# Smart_Project_Eagle.net
KiCad netlist of a schematic drawn in EasyEDA
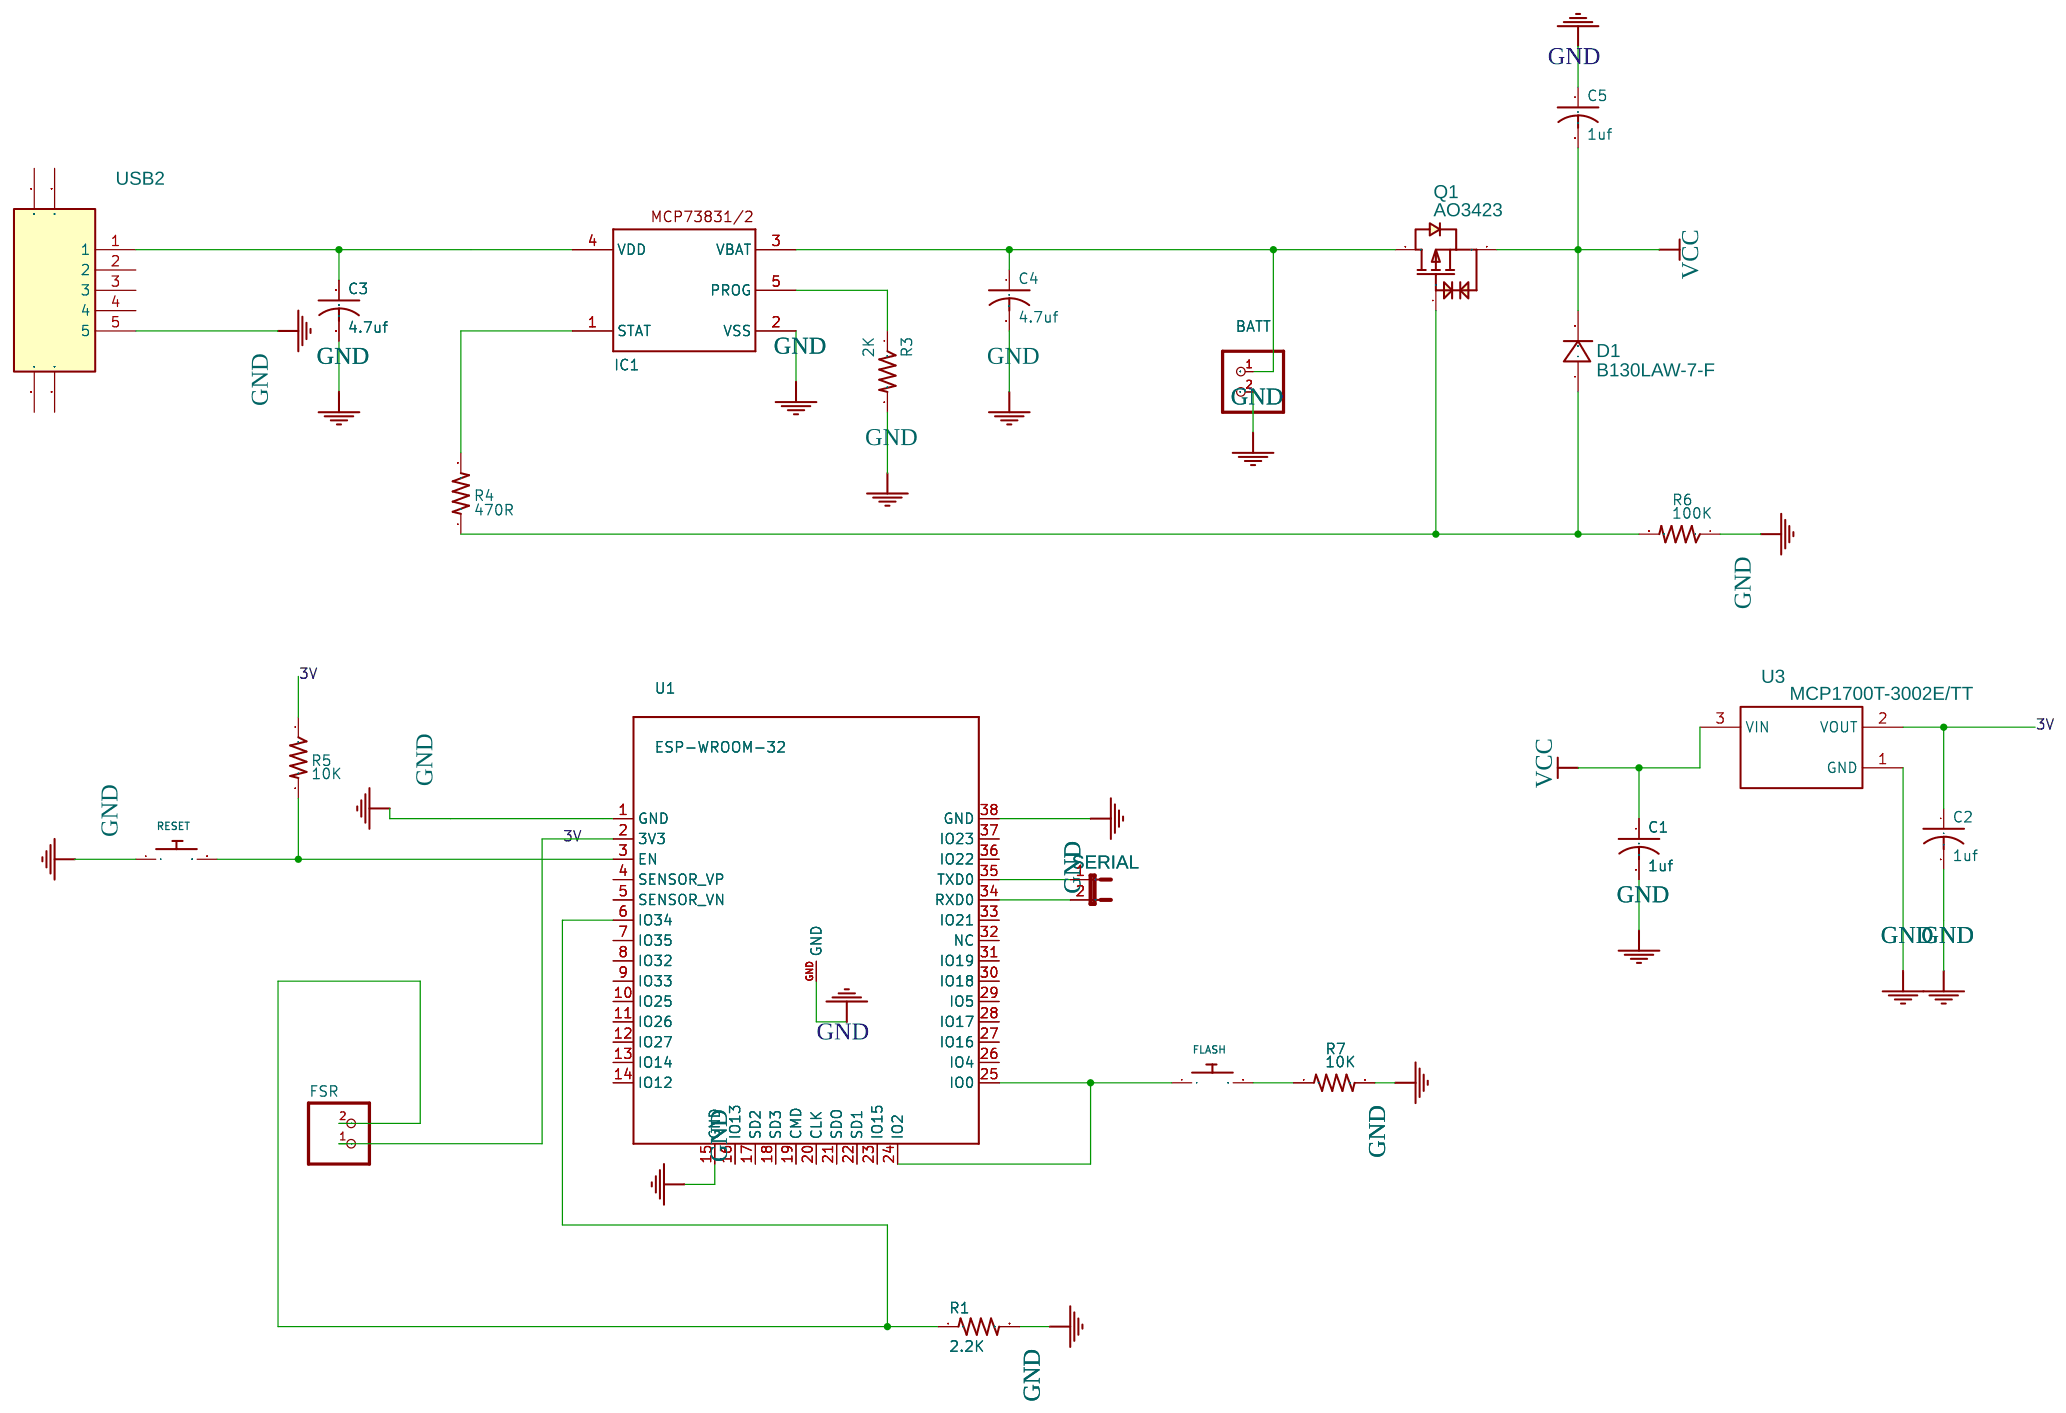
[diagram p0: schematic sheet]

(export (version "E")
  (design (tool "Eeschema 10.0.6"))
  (components
    (comp (ref "BATT") (value "JST_2PIN-SMT") (libsource (lib "") (part "Unknown_420_-470")))
    (comp (ref "C1") (value "1uf") (libsource (lib "") (part "Unknown_620_-240")))
    (comp (ref "C2") (value "1uf") (libsource (lib "") (part "Unknown_770_-245")))
    (comp (ref "C3") (value "4.7uf") (libsource (lib "") (part "Unknown_-20_-505")))
    (comp (ref "C4") (value "4.7uf") (libsource (lib "") (part "Unknown_310_-510")))
    (comp (ref "C5") (value "1uf") (libsource (lib "") (part "Unknown_590_-600")))
    (comp (ref "D1") (value "B130LAW-7-F") (libsource (lib "") (part "Unknown_590_-480")))
    (comp (ref "FLASH") (value "SWITCH_PUSHBUTTONC&K_KSS") (libsource (lib "") (part "Unknown_410_-120")))
    (comp (ref "FSR") (value "JST_2PIN-SMT") (libsource (lib "") (part "Unknown_-10_-90")))
    (comp (ref "IC1") (value "MCP73831/OT") (libsource (lib "") (part "Unknown_145_-510")))
    (comp (ref "JP1")
      (value "SERIAL")
      (fields (field (name "BOM_Manufacturer Part") "?"))
      (libsource (lib "") (part "Unknown_350_-220"))
    )
    (comp (ref "Q1") (value "AO3423") (libsource (lib "") (part "Unknown_520_-530")))
    (comp (ref "R1") (value "2.2K") (libsource (lib "") (part "Unknown_295_0")))
    (comp (ref "R3") (value "2K") (libsource (lib "") (part "Unknown_250_-470")))
    (comp (ref "R4") (value "470R") (libsource (lib "") (part "Unknown_40_-410")))
    (comp (ref "R5") (value "10K") (libsource (lib "") (part "Unknown_-40_-280")))
    (comp (ref "R6") (value "100K") (libsource (lib "") (part "Unknown_640_-390")))
    (comp (ref "R7") (value "10K") (libsource (lib "") (part "Unknown_470_-120")))
    (comp (ref "RESET") (value "SWITCH_PUSHBUTTONC&K_KSS") (libsource (lib "") (part "Unknown_-100_-230")))
    (comp (ref "U1") (value "ESP-WROOM-32") (libsource (lib "") (part "Unknown_185_-240")))
    (comp (ref "U3") (value "MCP1700T-3002E/TT") (libsource (lib "") (part "Unknown_700_-305")))
    (comp (ref "USB2")
      (value "micro 5PAll posts are not guided Flat welding_C40942")
      (fields (field (name "BOM_Manufacturer Part") "micro 5PAll posts are not guided Flat welding"))
      (libsource (lib "") (part "Unknown_-160_-510"))
    )
  )
  (nets
    (net (code "1") (name "/3V") (class "Default")
      (node (ref "C2") (pin "1") (pinfunction "1_1") (pintype "bidirectional"))
      (node (ref "FSR") (pin "1") (pinfunction "2_1") (pintype "bidirectional"))
      (node (ref "R5") (pin "1") (pinfunction "1_1") (pintype "bidirectional"))
      (node (ref "U1") (pin "2") (pinfunction "3V3_2") (pintype "bidirectional"))
      (node (ref "U3") (pin "2") (pinfunction "VOUT_2") (pintype "passive"))
    )
    (net (code "2") (name "GND") (class "Default")
      (node (ref "BATT") (pin "2") (pinfunction "1_2") (pintype "bidirectional"))
      (node (ref "C1") (pin "2") (pinfunction "2_2") (pintype "bidirectional"))
      (node (ref "C2") (pin "2") (pinfunction "2_2") (pintype "bidirectional"))
      (node (ref "C3") (pin "2") (pinfunction "2_2") (pintype "bidirectional"))
      (node (ref "C4") (pin "2") (pinfunction "2_2") (pintype "bidirectional"))
      (node (ref "C5") (pin "1") (pinfunction "1_1") (pintype "bidirectional"))
      (node (ref "IC1") (pin "2") (pinfunction "VSS_2") (pintype "bidirectional"))
      (node (ref "R1") (pin "2") (pinfunction "2_2") (pintype "bidirectional"))
      (node (ref "R3") (pin "2") (pinfunction "2_2") (pintype "bidirectional"))
      (node (ref "R6") (pin "1") (pinfunction "1_1") (pintype "bidirectional"))
      (node (ref "R7") (pin "2") (pinfunction "2_2") (pintype "bidirectional"))
      (node (ref "RESET") (pin "1") (pinfunction "1_1") (pintype "bidirectional"))
      (node (ref "U1") (pin "1") (pinfunction "GND_1") (pintype "bidirectional"))
      (node (ref "U1") (pin "15") (pinfunction "GND_15") (pintype "bidirectional"))
      (node (ref "U1") (pin "38") (pinfunction "GND_38") (pintype "bidirectional"))
      (node (ref "U1") (pin "GND") (pinfunction "GND_GND") (pintype "bidirectional"))
      (node (ref "U3") (pin "1") (pinfunction "GND_1") (pintype "passive"))
      (node (ref "USB2") (pin "5") (pinfunction "5_5") (pintype "unspecified"))
    )
    (net (code "3") (name "Net-(BATT-2)") (class "Default")
      (node (ref "BATT") (pin "1") (pinfunction "2_1") (pintype "bidirectional"))
      (node (ref "C4") (pin "1") (pinfunction "1_1") (pintype "bidirectional"))
      (node (ref "IC1") (pin "3") (pinfunction "VBAT_3") (pintype "bidirectional"))
      (node (ref "Q1") (pin "3") (pinfunction "D_3") (pintype "unspecified"))
    )
    (net (code "4") (name "Net-(FLASH-Pad2)") (class "Default")
      (node (ref "FLASH") (pin "2") (pinfunction "2_2") (pintype "bidirectional"))
      (node (ref "R7") (pin "1") (pinfunction "1_1") (pintype "bidirectional"))
    )
    (net (code "5") (name "Net-(FSR-1)") (class "Default")
      (node (ref "FSR") (pin "2") (pinfunction "1_2") (pintype "bidirectional"))
      (node (ref "R1") (pin "1") (pinfunction "1_1") (pintype "bidirectional"))
      (node (ref "U1") (pin "6") (pinfunction "IO34_6") (pintype "bidirectional"))
    )
    (net (code "6") (name "Net-(IC1-PROG)") (class "Default")
      (node (ref "IC1") (pin "5") (pinfunction "PROG_5") (pintype "bidirectional"))
      (node (ref "R3") (pin "1") (pinfunction "1_1") (pintype "bidirectional"))
    )
    (net (code "7") (name "Net-(IC1-STAT)") (class "Default")
      (node (ref "IC1") (pin "1") (pinfunction "STAT_1") (pintype "bidirectional"))
      (node (ref "R4") (pin "2") (pinfunction "2_2") (pintype "bidirectional"))
    )
    (net (code "8") (name "Net-(IC1-VDD)") (class "Default")
      (node (ref "C3") (pin "1") (pinfunction "1_1") (pintype "bidirectional"))
      (node (ref "IC1") (pin "4") (pinfunction "VDD_4") (pintype "bidirectional"))
      (node (ref "USB2") (pin "1") (pinfunction "1_1") (pintype "unspecified"))
    )
    (net (code "9") (name "Net-(Q1-G)") (class "Default")
      (node (ref "D1") (pin "1") (pinfunction "1_1") (pintype "unspecified"))
      (node (ref "Q1") (pin "1") (pinfunction "G_1") (pintype "unspecified"))
      (node (ref "R4") (pin "1") (pinfunction "1_1") (pintype "bidirectional"))
      (node (ref "R6") (pin "2") (pinfunction "2_2") (pintype "bidirectional"))
    )
    (net (code "10") (name "Net-(U1-EN)") (class "Default")
      (node (ref "R5") (pin "2") (pinfunction "2_2") (pintype "bidirectional"))
      (node (ref "RESET") (pin "2") (pinfunction "2_2") (pintype "bidirectional"))
      (node (ref "U1") (pin "3") (pinfunction "EN_3") (pintype "bidirectional"))
    )
    (net (code "11") (name "Net-(U1-IO0)") (class "Default")
      (node (ref "FLASH") (pin "1") (pinfunction "1_1") (pintype "bidirectional"))
      (node (ref "U1") (pin "24") (pinfunction "IO2_24") (pintype "bidirectional"))
      (node (ref "U1") (pin "25") (pinfunction "IO0_25") (pintype "bidirectional"))
    )
    (net (code "12") (name "Net-(U1-RXD0)") (class "Default")
      (node (ref "JP1") (pin "2") (pinfunction "2_2") (pintype "unspecified"))
      (node (ref "U1") (pin "34") (pinfunction "RXD0_34") (pintype "bidirectional"))
    )
    (net (code "13") (name "Net-(U1-TXD0)") (class "Default")
      (node (ref "JP1") (pin "1") (pinfunction "1_1") (pintype "unspecified"))
      (node (ref "U1") (pin "35") (pinfunction "TXD0_35") (pintype "bidirectional"))
    )
    (net (code "14") (name "VCC") (class "Default")
      (node (ref "C1") (pin "1") (pinfunction "1_1") (pintype "bidirectional"))
      (node (ref "C5") (pin "2") (pinfunction "2_2") (pintype "bidirectional"))
      (node (ref "D1") (pin "2") (pinfunction "2_2") (pintype "unspecified"))
      (node (ref "Q1") (pin "2") (pinfunction "S_2") (pintype "unspecified"))
      (node (ref "U3") (pin "3") (pinfunction "VIN_3") (pintype "passive"))
    )
    (net (code "15") (name "unconnected-(U1-CLK-Pad20)") (class "Default")
      (node (ref "U1") (pin "20") (pinfunction "CLK_20") (pintype "bidirectional"))
    )
    (net (code "16") (name "unconnected-(U1-CMD-Pad19)") (class "Default")
      (node (ref "U1") (pin "19") (pinfunction "CMD_19") (pintype "bidirectional"))
    )
    (net (code "17") (name "unconnected-(U1-IO4-Pad26)") (class "Default")
      (node (ref "U1") (pin "26") (pinfunction "IO4_26") (pintype "bidirectional"))
    )
    (net (code "18") (name "unconnected-(U1-IO5-Pad29)") (class "Default")
      (node (ref "U1") (pin "29") (pinfunction "IO5_29") (pintype "bidirectional"))
    )
    (net (code "19") (name "unconnected-(U1-IO12-Pad14)") (class "Default")
      (node (ref "U1") (pin "14") (pinfunction "IO12_14") (pintype "bidirectional"))
    )
    (net (code "20") (name "unconnected-(U1-IO13-Pad16)") (class "Default")
      (node (ref "U1") (pin "16") (pinfunction "IO13_16") (pintype "bidirectional"))
    )
    (net (code "21") (name "unconnected-(U1-IO14-Pad13)") (class "Default")
      (node (ref "U1") (pin "13") (pinfunction "IO14_13") (pintype "bidirectional"))
    )
    (net (code "22") (name "unconnected-(U1-IO15-Pad23)") (class "Default")
      (node (ref "U1") (pin "23") (pinfunction "IO15_23") (pintype "bidirectional"))
    )
    (net (code "23") (name "unconnected-(U1-IO16-Pad27)") (class "Default")
      (node (ref "U1") (pin "27") (pinfunction "IO16_27") (pintype "bidirectional"))
    )
    (net (code "24") (name "unconnected-(U1-IO17-Pad28)") (class "Default")
      (node (ref "U1") (pin "28") (pinfunction "IO17_28") (pintype "bidirectional"))
    )
    (net (code "25") (name "unconnected-(U1-IO18-Pad30)") (class "Default")
      (node (ref "U1") (pin "30") (pinfunction "IO18_30") (pintype "bidirectional"))
    )
    (net (code "26") (name "unconnected-(U1-IO19-Pad31)") (class "Default")
      (node (ref "U1") (pin "31") (pinfunction "IO19_31") (pintype "bidirectional"))
    )
    (net (code "27") (name "unconnected-(U1-IO21-Pad33)") (class "Default")
      (node (ref "U1") (pin "33") (pinfunction "IO21_33") (pintype "bidirectional"))
    )
    (net (code "28") (name "unconnected-(U1-IO22-Pad36)") (class "Default")
      (node (ref "U1") (pin "36") (pinfunction "IO22_36") (pintype "bidirectional"))
    )
    (net (code "29") (name "unconnected-(U1-IO23-Pad37)") (class "Default")
      (node (ref "U1") (pin "37") (pinfunction "IO23_37") (pintype "bidirectional"))
    )
    (net (code "30") (name "unconnected-(U1-IO25-Pad10)") (class "Default")
      (node (ref "U1") (pin "10") (pinfunction "IO25_10") (pintype "bidirectional"))
    )
    (net (code "31") (name "unconnected-(U1-IO26-Pad11)") (class "Default")
      (node (ref "U1") (pin "11") (pinfunction "IO26_11") (pintype "bidirectional"))
    )
    (net (code "32") (name "unconnected-(U1-IO27-Pad12)") (class "Default")
      (node (ref "U1") (pin "12") (pinfunction "IO27_12") (pintype "bidirectional"))
    )
    (net (code "33") (name "unconnected-(U1-IO32-Pad8)") (class "Default")
      (node (ref "U1") (pin "8") (pinfunction "IO32_8") (pintype "bidirectional"))
    )
    (net (code "34") (name "unconnected-(U1-IO33-Pad9)") (class "Default")
      (node (ref "U1") (pin "9") (pinfunction "IO33_9") (pintype "bidirectional"))
    )
    (net (code "35") (name "unconnected-(U1-IO35-Pad7)") (class "Default")
      (node (ref "U1") (pin "7") (pinfunction "IO35_7") (pintype "bidirectional"))
    )
    (net (code "36") (name "unconnected-(U1-NC-Pad32)") (class "Default")
      (node (ref "U1") (pin "32") (pinfunction "NC_32") (pintype "bidirectional"))
    )
    (net (code "37") (name "unconnected-(U1-SD1-Pad22)") (class "Default")
      (node (ref "U1") (pin "22") (pinfunction "SD1_22") (pintype "bidirectional"))
    )
    (net (code "38") (name "unconnected-(U1-SD2-Pad17)") (class "Default")
      (node (ref "U1") (pin "17") (pinfunction "SD2_17") (pintype "bidirectional"))
    )
    (net (code "39") (name "unconnected-(U1-SD3-Pad18)") (class "Default")
      (node (ref "U1") (pin "18") (pinfunction "SD3_18") (pintype "bidirectional"))
    )
    (net (code "40") (name "unconnected-(U1-SDO-Pad21)") (class "Default")
      (node (ref "U1") (pin "21") (pinfunction "SDO_21") (pintype "bidirectional"))
    )
    (net (code "41") (name "unconnected-(U1-SENSOR_VN-Pad5)") (class "Default")
      (node (ref "U1") (pin "5") (pinfunction "SENSOR_VN_5") (pintype "bidirectional"))
    )
    (net (code "42") (name "unconnected-(U1-SENSOR_VP-Pad4)") (class "Default")
      (node (ref "U1") (pin "4") (pinfunction "SENSOR_VP_4") (pintype "bidirectional"))
    )
    (net (code "43") (name "unconnected-(USB2-Pad0)") (class "Default")
      (node (ref "USB2") (pin "0") (pinfunction "0_0") (pintype "input"))
    )
    (net (code "44") (name "unconnected-(USB2-Pad0)_1") (class "Default")
      (node (ref "USB2") (pin "0") (pinfunction "0_0") (pintype "input"))
    )
    (net (code "45") (name "unconnected-(USB2-Pad0)_2") (class "Default")
      (node (ref "USB2") (pin "0") (pinfunction "0_0") (pintype "input"))
    )
    (net (code "46") (name "unconnected-(USB2-Pad0)_3") (class "Default")
      (node (ref "USB2") (pin "0") (pinfunction "0_0") (pintype "input"))
    )
    (net (code "47") (name "unconnected-(USB2-Pad2)") (class "Default")
      (node (ref "USB2") (pin "2") (pinfunction "2_2") (pintype "unspecified"))
    )
    (net (code "48") (name "unconnected-(USB2-Pad3)") (class "Default")
      (node (ref "USB2") (pin "3") (pinfunction "3_3") (pintype "unspecified"))
    )
    (net (code "49") (name "unconnected-(USB2-Pad4)") (class "Default")
      (node (ref "USB2") (pin "4") (pinfunction "4_4") (pintype "unspecified"))
    )
  )
)
